# dm4_midi_brk_v1.net
KiCad netlist of a schematic drawn in EAGLE
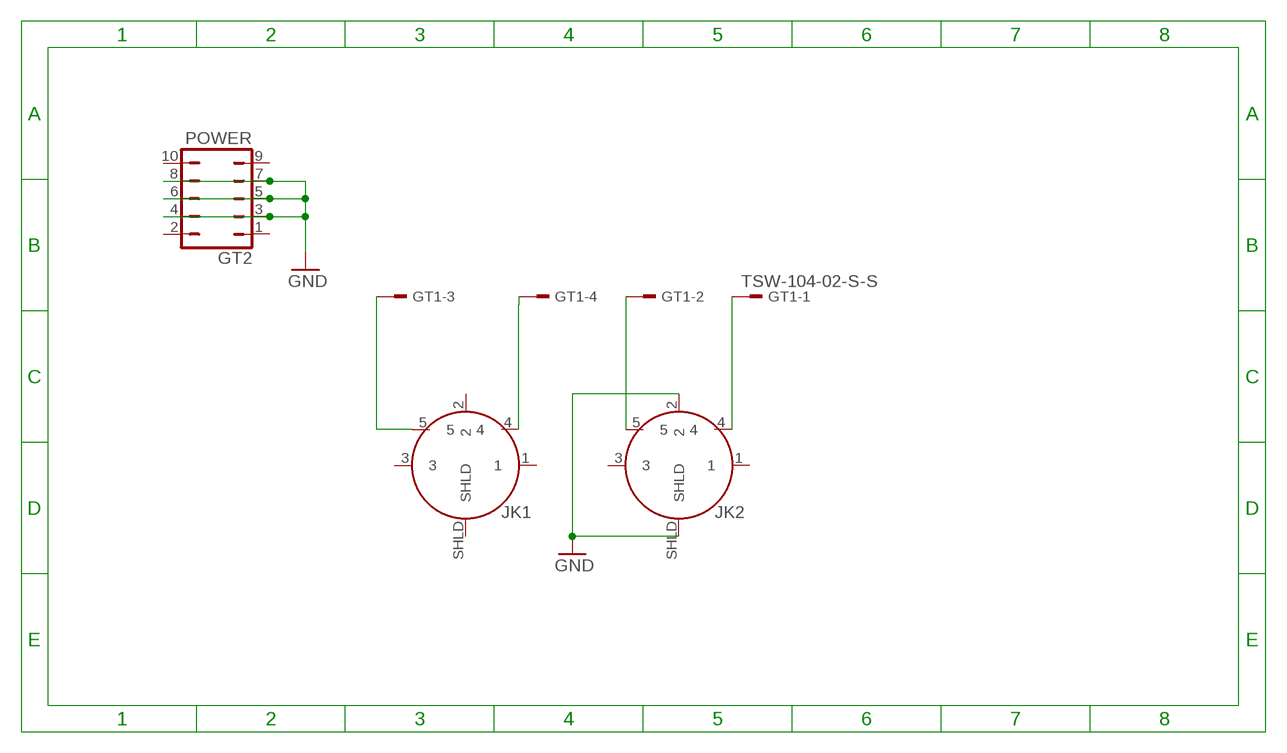
[diagram p0: schematic, sheet 1]

(export (version "E")
  (design (tool "Eeschema 10.0.6"))
  (components
    (comp (ref "GT1")
      (value "TSW-104-02-S-S")
      (footprint "eagle-import:TSW-104-02-S-S")
      (libsource (lib "eagle-import") (part "TSW-104-02-S-S"))
    )
    (comp (ref "GT2")
      (value "POWER")
      (footprint "eagle-import:JP5Q")
      (libsource (lib "eagle-import") (part "JP5Q"))
    )
    (comp (ref "JK1")
      (value "13HP021PCB")
      (footprint "eagle-import:13HP021PCB")
      (libsource (lib "eagle-import") (part "13HP021PCB"))
    )
    (comp (ref "JK2")
      (value "13HP021PCB")
      (footprint "eagle-import:13HP021PCB")
      (libsource (lib "eagle-import") (part "13HP021PCB"))
    )
  )
  (nets
    (net (code "1") (name "GND") (class "Default")
      (node (ref "GT2") (pin "3") (pinfunction "3_3") (pintype "passive"))
      (node (ref "GT2") (pin "4") (pinfunction "4_4") (pintype "passive"))
      (node (ref "GT2") (pin "5") (pinfunction "5_5") (pintype "passive"))
      (node (ref "GT2") (pin "6") (pinfunction "6_6") (pintype "passive"))
      (node (ref "GT2") (pin "7") (pinfunction "7_7") (pintype "passive"))
      (node (ref "GT2") (pin "8") (pinfunction "8_8") (pintype "passive"))
      (node (ref "JK2") (pin "2") (pinfunction "2_2") (pintype "passive"))
      (node (ref "JK2") (pin "SHLD") (pinfunction "SHLD_SHLD") (pintype "passive"))
    )
    (net (code "2") (name "Net-(GT1-Pad1)") (class "Default")
      (node (ref "GT1") (pin "1") (pinfunction "1_1") (pintype "passive"))
      (node (ref "JK2") (pin "4") (pinfunction "4_4") (pintype "passive"))
    )
    (net (code "3") (name "Net-(GT1B-1)") (class "Default")
      (node (ref "GT1") (pin "2") (pinfunction "1_2") (pintype "passive"))
      (node (ref "JK2") (pin "5") (pinfunction "5_5") (pintype "passive"))
    )
    (net (code "4") (name "Net-(GT1C-1)") (class "Default")
      (node (ref "GT1") (pin "3") (pinfunction "1_3") (pintype "passive"))
      (node (ref "JK1") (pin "5") (pinfunction "5_5") (pintype "passive"))
    )
    (net (code "5") (name "Net-(GT1D-1)") (class "Default")
      (node (ref "GT1") (pin "4") (pinfunction "1_4") (pintype "passive"))
      (node (ref "JK1") (pin "4") (pinfunction "4_4") (pintype "passive"))
    )
    (net (code "6") (name "unconnected-(GT2-Pad1)") (class "Default")
      (node (ref "GT2") (pin "1") (pinfunction "1_1") (pintype "passive"))
    )
    (net (code "7") (name "unconnected-(GT2-Pad2)") (class "Default")
      (node (ref "GT2") (pin "2") (pinfunction "2_2") (pintype "passive"))
    )
    (net (code "8") (name "unconnected-(GT2-Pad9)") (class "Default")
      (node (ref "GT2") (pin "9") (pinfunction "9_9") (pintype "passive"))
    )
    (net (code "9") (name "unconnected-(GT2-Pad10)") (class "Default")
      (node (ref "GT2") (pin "10") (pinfunction "10_10") (pintype "passive"))
    )
    (net (code "10") (name "unconnected-(JK1-Pad1)") (class "Default")
      (node (ref "JK1") (pin "1") (pinfunction "1_1") (pintype "passive"))
    )
    (net (code "11") (name "unconnected-(JK1-Pad2)") (class "Default")
      (node (ref "JK1") (pin "2") (pinfunction "2_2") (pintype "passive"))
    )
    (net (code "12") (name "unconnected-(JK1-Pad3)") (class "Default")
      (node (ref "JK1") (pin "3") (pinfunction "3_3") (pintype "passive"))
    )
    (net (code "13") (name "unconnected-(JK1-PadSHLD)") (class "Default")
      (node (ref "JK1") (pin "SHLD") (pinfunction "SHLD_SHLD") (pintype "passive"))
    )
    (net (code "14") (name "unconnected-(JK2-Pad1)") (class "Default")
      (node (ref "JK2") (pin "1") (pinfunction "1_1") (pintype "passive"))
    )
    (net (code "15") (name "unconnected-(JK2-Pad3)") (class "Default")
      (node (ref "JK2") (pin "3") (pinfunction "3_3") (pintype "passive"))
    )
  )
)
